# soundfield_board_40720_25mm.net
KiCad netlist of a schematic drawn in EAGLE
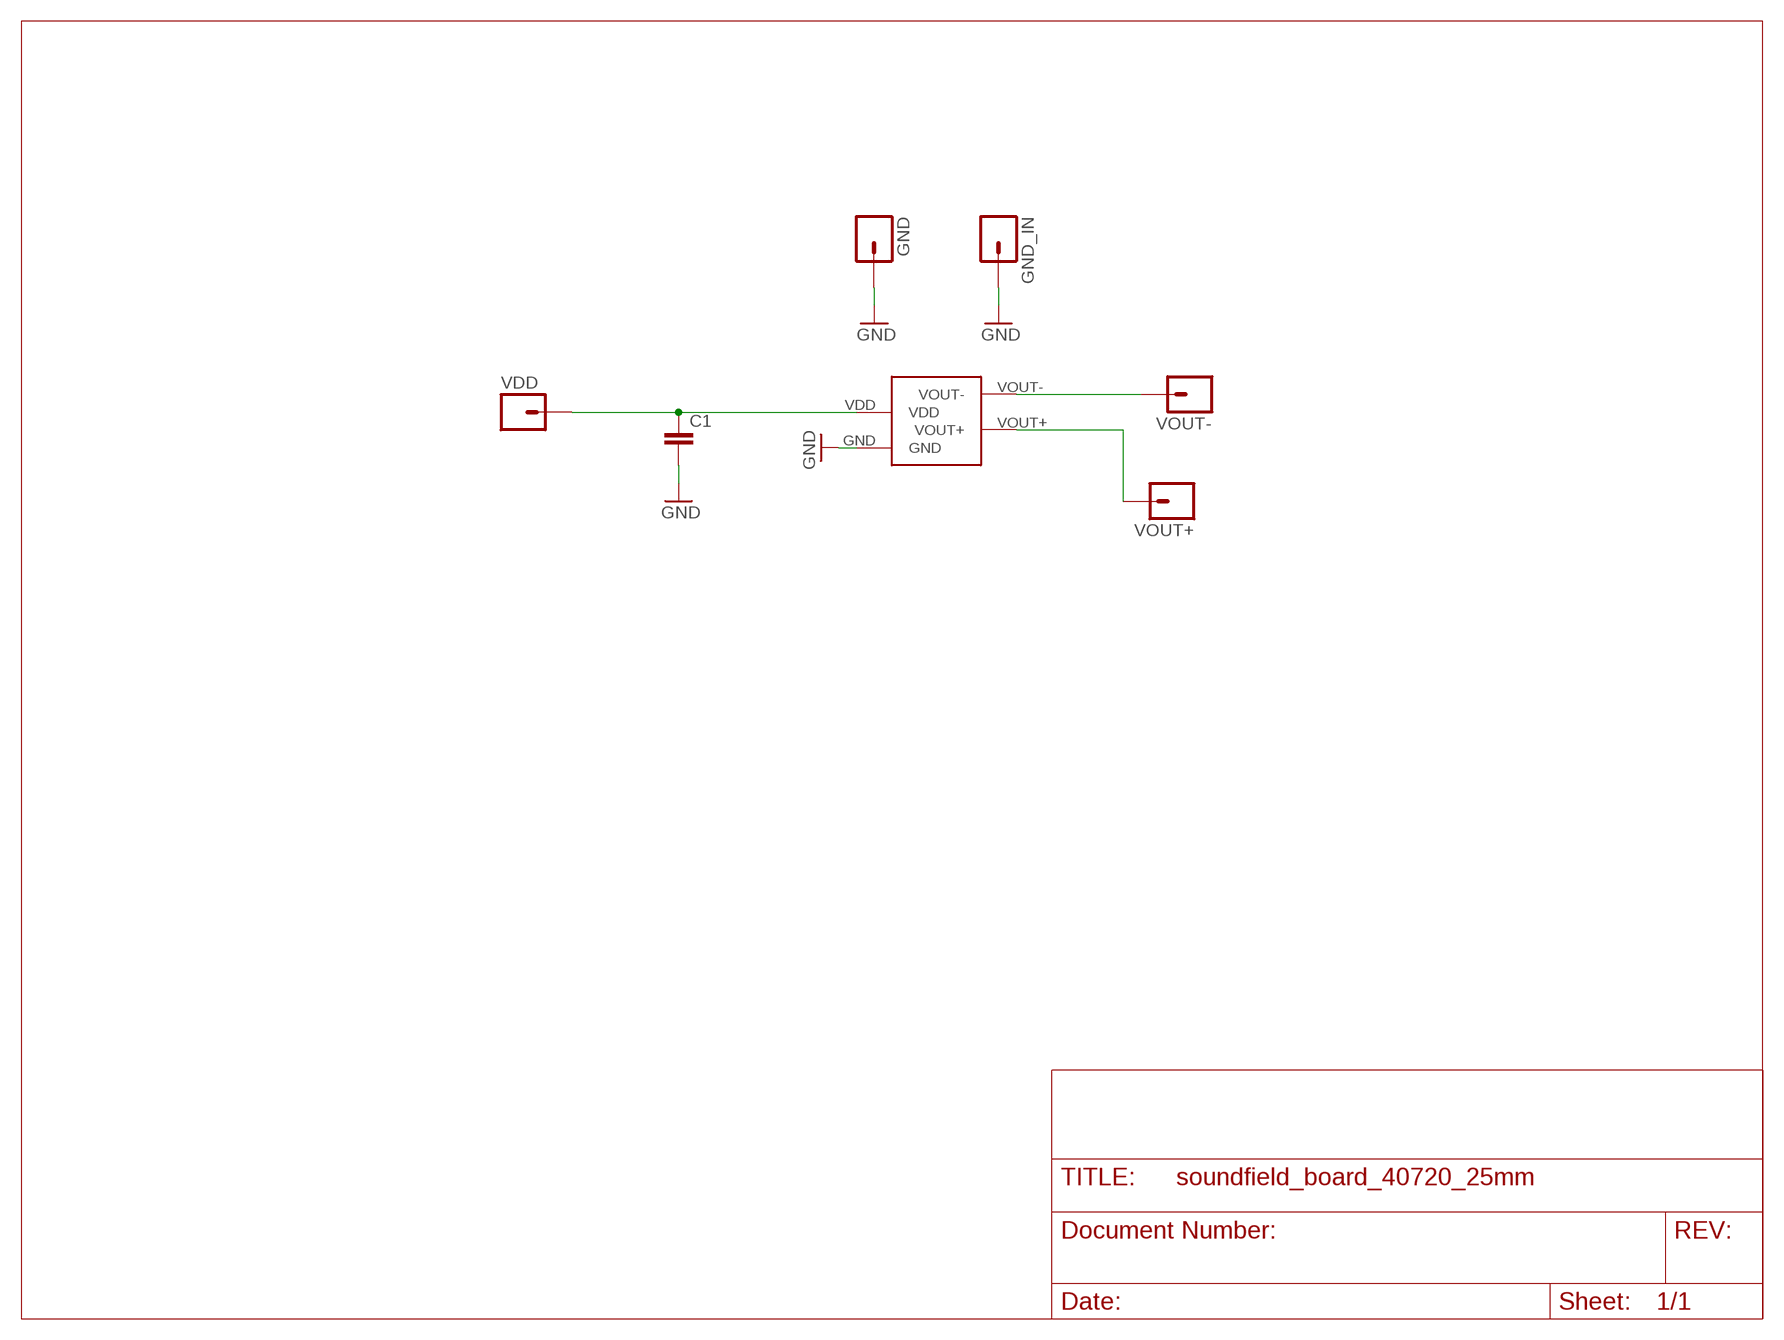
[diagram p0: schematic, sheet 1]

(export (version "E")
  (design (tool "Eeschema 10.0.6"))
  (components
    (comp (ref "C1")
      (value "0.1UF-16V(+-10%)(0402)")
      (footprint "eagle-import:0402-CAP")
      (libsource (lib "eagle-import") (part "0.1UF-16V(+-10%)(0402)"))
    )
    (comp (ref "GND")
      (value "M01PTH_NO_SILK_YES_STOP")
      (footprint "eagle-import:1X01_NO_SILK")
      (libsource (lib "eagle-import") (part "CM-SparkFun-Connectors-large_hole_M01PTH_NO_SILK_YES_STOP"))
    )
    (comp (ref "GND_IN")
      (value "M01PTH_2MM")
      (footprint "eagle-import:1X01_2MM")
      (libsource (lib "eagle-import") (part "CM-SparkFun-Connectors-2_M01PTH_2MM"))
    )
    (comp (ref "U$1")
      (value "MEMS_ICS_40720")
      (footprint "eagle-import: MEMS_ICS_40720")
      (libsource (lib "eagle-import") (part " MEMS_ICS_40720"))
    )
    (comp (ref "VDD")
      (value "M01PTH_2MM")
      (footprint "eagle-import:1X01_2MM")
      (libsource (lib "eagle-import") (part "M01PTH_2MM"))
    )
    (comp (ref "VOUT+")
      (value "M01PTH_2MM")
      (footprint "eagle-import:1X01_2MM")
      (libsource (lib "eagle-import") (part "M01PTH_2MM"))
    )
    (comp (ref "VOUT-")
      (value "M01PTH_2MM")
      (footprint "eagle-import:1X01_2MM")
      (libsource (lib "eagle-import") (part "M01PTH_2MM"))
    )
  )
  (nets
    (net (code "1") (name "GND") (class "Default")
      (node (ref "C1") (pin "2") (pinfunction "2_2") (pintype "passive"))
      (node (ref "GND") (pin "1") (pinfunction "1_1") (pintype "passive"))
      (node (ref "GND_IN") (pin "1") (pinfunction "1_1") (pintype "passive"))
      (node (ref "U$1") (pin "GND") (pinfunction "GND_GND") (pintype "input"))
    )
    (net (code "2") (name "Net-(C1-Pad1)") (class "Default")
      (node (ref "C1") (pin "1") (pinfunction "1_1") (pintype "passive"))
      (node (ref "U$1") (pin "VDD") (pinfunction "VDD_VDD") (pintype "power_in"))
      (node (ref "VDD") (pin "1") (pinfunction "1_1") (pintype "passive"))
    )
    (net (code "3") (name "Net-(U$1-PadVOUT+)") (class "Default")
      (node (ref "U$1") (pin "VOUT+") (pinfunction "VOUT+_VOUT+") (pintype "input"))
      (node (ref "VOUT+") (pin "1") (pinfunction "1_1") (pintype "passive"))
    )
    (net (code "4") (name "Net-(U$1-PadVOUT-)") (class "Default")
      (node (ref "U$1") (pin "VOUT-") (pinfunction "VOUT-_VOUT-") (pintype "input"))
      (node (ref "VOUT-") (pin "1") (pinfunction "1_1") (pintype "passive"))
    )
  )
)
